# MCU.net
KiCad netlist of a schematic drawn in Altium Designer
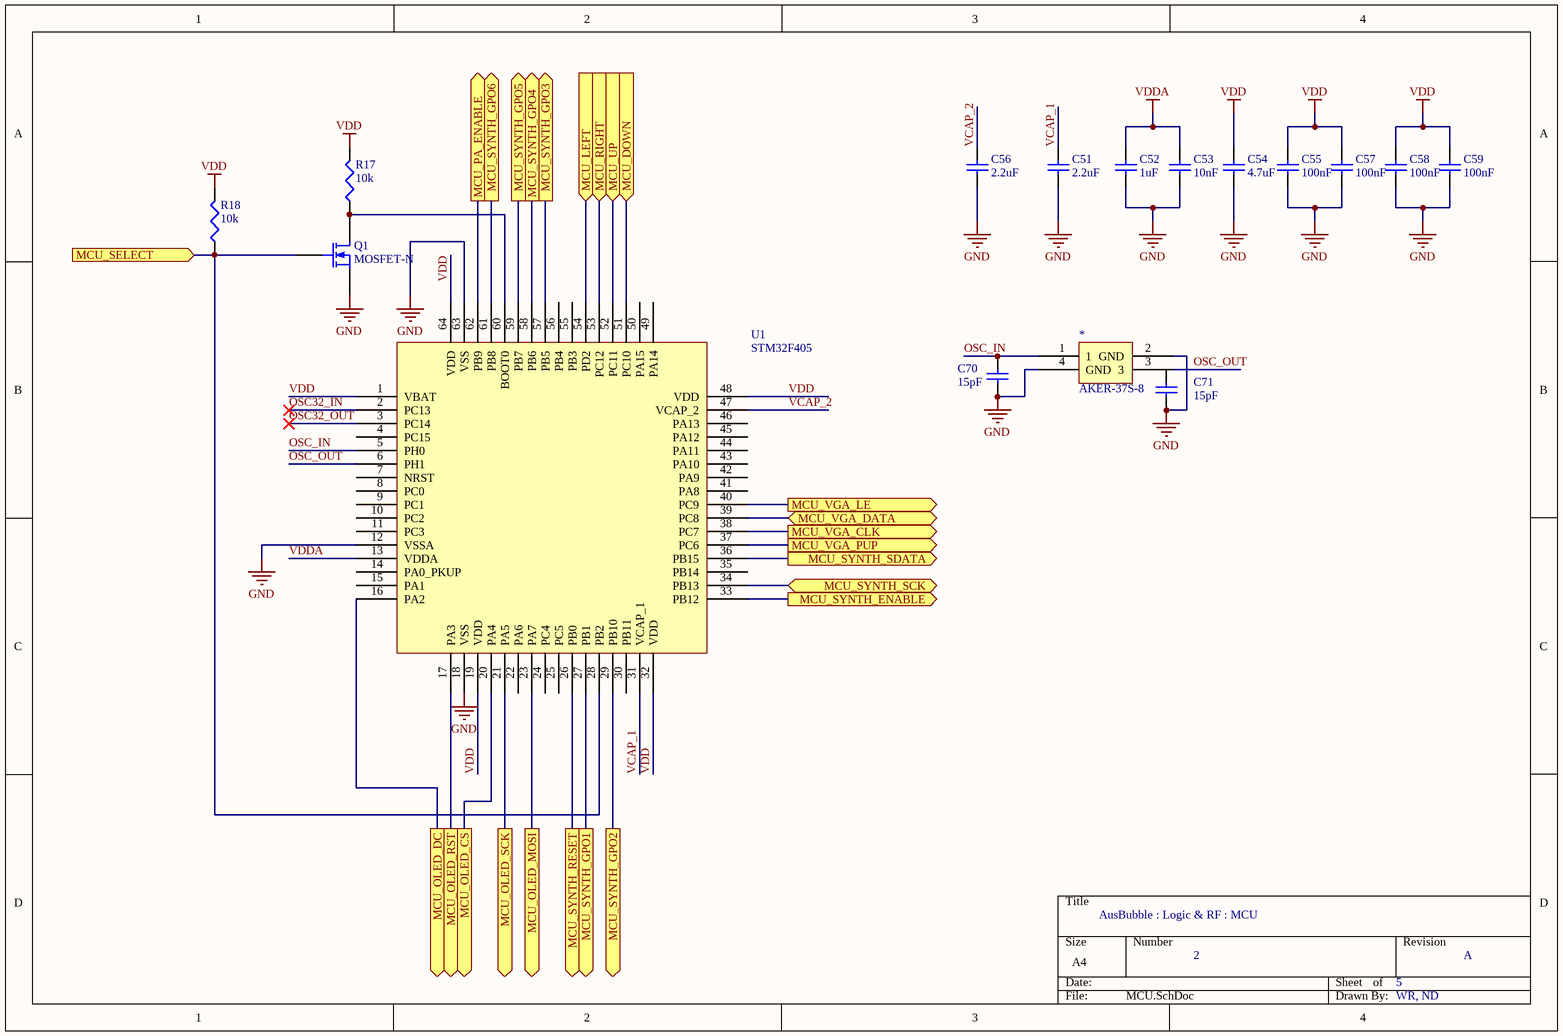
[diagram p0: MCU.SchDoc]

(export (version "E")
  (design (tool "Eeschema 10.0.6"))
  (components
    (comp (ref "*")
      (value "AKER-37S-8")
      (footprint "AKER-37S")
      (libsource (lib "Logic_RF_Component_Symbols") (part "AKER-37S-8"))
    )
    (comp (ref "C51")
      (value "2.2uF")
      (footprint "1608[0603]")
      (description "Capacitor (Semiconductor SIM Model)")
      (fields (field (name "Comment") "Cap Semi") (field (name "PUBLISHER") "Altium Limited"))
      (libsource (lib "Miscellaneous Devices") (part "Cap Semi"))
    )
    (comp (ref "C52")
      (value "1uF")
      (footprint "1608[0603]")
      (description "Capacitor (Semiconductor SIM Model)")
      (fields (field (name "Comment") "Cap Semi") (field (name "PUBLISHER") "Altium Limited"))
      (libsource (lib "Miscellaneous Devices") (part "Cap Semi"))
    )
    (comp (ref "C53")
      (value "10nF")
      (footprint "1608[0603]")
      (description "Capacitor (Semiconductor SIM Model)")
      (fields (field (name "Comment") "Cap Semi") (field (name "PUBLISHER") "Altium Limited"))
      (libsource (lib "Miscellaneous Devices") (part "Cap Semi"))
    )
    (comp (ref "C54")
      (value "4.7uF")
      (footprint "1608[0603]")
      (description "Capacitor (Semiconductor SIM Model)")
      (fields (field (name "Comment") "Cap Semi") (field (name "PUBLISHER") "Altium Limited"))
      (libsource (lib "Miscellaneous Devices") (part "Cap Semi"))
    )
    (comp (ref "C55")
      (value "100nF")
      (footprint "1608[0603]")
      (description "Capacitor (Semiconductor SIM Model)")
      (fields (field (name "Comment") "Cap Semi") (field (name "PUBLISHER") "Altium Limited"))
      (libsource (lib "Miscellaneous Devices") (part "Cap Semi"))
    )
    (comp (ref "C56")
      (value "2.2uF")
      (footprint "1608[0603]")
      (description "Capacitor (Semiconductor SIM Model)")
      (fields (field (name "Comment") "Cap Semi") (field (name "PUBLISHER") "Altium Limited"))
      (libsource (lib "Miscellaneous Devices") (part "Cap Semi"))
    )
    (comp (ref "C57")
      (value "100nF")
      (footprint "1608[0603]")
      (description "Capacitor (Semiconductor SIM Model)")
      (fields (field (name "Comment") "Cap Semi") (field (name "PUBLISHER") "Altium Limited"))
      (libsource (lib "Miscellaneous Devices") (part "Cap Semi"))
    )
    (comp (ref "C58")
      (value "100nF")
      (footprint "1608[0603]")
      (description "Capacitor (Semiconductor SIM Model)")
      (fields (field (name "Comment") "Cap Semi") (field (name "PUBLISHER") "Altium Limited"))
      (libsource (lib "Miscellaneous Devices") (part "Cap Semi"))
    )
    (comp (ref "C59")
      (value "100nF")
      (footprint "1608[0603]")
      (description "Capacitor (Semiconductor SIM Model)")
      (fields (field (name "Comment") "Cap Semi") (field (name "PUBLISHER") "Altium Limited"))
      (libsource (lib "Miscellaneous Devices") (part "Cap Semi"))
    )
    (comp (ref "C70")
      (value "15pF")
      (footprint "0402")
      (description "Capacitor (Semiconductor SIM Model)")
      (fields (field (name "Comment") "Cap Semi") (field (name "PUBLISHER") "Altium Limited"))
      (libsource (lib "Miscellaneous Devices") (part "Cap Semi"))
    )
    (comp (ref "C71")
      (value "15pF")
      (footprint "0402")
      (description "Capacitor (Semiconductor SIM Model)")
      (fields (field (name "Comment") "Cap Semi") (field (name "PUBLISHER") "Altium Limited"))
      (libsource (lib "Miscellaneous Devices") (part "Cap Semi"))
    )
    (comp (ref "Q1")
      (value "MOSFET-N")
      (footprint "SOT95P230-3M")
      (description "N-Channel MOSFET")
      (fields (field (name "PUBLISHER") "Altium Limited"))
      (libsource (lib "Miscellaneous Devices") (part "MOSFET-N"))
    )
    (comp (ref "R17")
      (value "10k")
      (footprint "J1-0603")
      (description "Resistor")
      (fields (field (name "Comment") "Res3") (field (name "PUBLISHER") "Altium Limited"))
      (libsource (lib "Miscellaneous Devices") (part "Res3"))
    )
    (comp (ref "R18")
      (value "10k")
      (footprint "J1-0603")
      (description "Resistor")
      (fields (field (name "Comment") "Res3") (field (name "PUBLISHER") "Altium Limited"))
      (libsource (lib "Miscellaneous Devices") (part "Res3"))
    )
    (comp (ref "U1")
      (value "STM32F405")
      (footprint "SQFP50P1200X1200-64L")
      (description "ARM Cortex-M4 32 bit Microprocessor")
      (libsource (lib "Logic_RF_Component_Symbols") (part "STM32F405RG"))
    )
  )
  (nets
    (net (code "1") (name "/MCU_DOWN") (class "Default")
      (node (ref "U1") (pin "51") (pinfunction "PC10_51") (pintype "passive"))
    )
    (net (code "2") (name "/MCU_LEFT") (class "Default")
      (node (ref "U1") (pin "54") (pinfunction "PD2_54") (pintype "passive"))
    )
    (net (code "3") (name "/MCU_OLED_CS") (class "Default")
      (node (ref "U1") (pin "20") (pinfunction "PA4_20") (pintype "passive"))
    )
    (net (code "4") (name "/MCU_OLED_DC") (class "Default")
      (node (ref "U1") (pin "16") (pinfunction "PA2_16") (pintype "passive"))
    )
    (net (code "5") (name "/MCU_OLED_MOSI") (class "Default")
      (node (ref "U1") (pin "23") (pinfunction "PA7_23") (pintype "passive"))
    )
    (net (code "6") (name "/MCU_OLED_RST") (class "Default")
      (node (ref "U1") (pin "17") (pinfunction "PA3_17") (pintype "passive"))
    )
    (net (code "7") (name "/MCU_OLED_SCK") (class "Default")
      (node (ref "U1") (pin "21") (pinfunction "PA5_21") (pintype "passive"))
    )
    (net (code "8") (name "/MCU_PA_ENABLE") (class "Default")
      (node (ref "U1") (pin "62") (pinfunction "PB9_62") (pintype "passive"))
    )
    (net (code "9") (name "/MCU_RIGHT") (class "Default")
      (node (ref "U1") (pin "53") (pinfunction "PC12_53") (pintype "passive"))
    )
    (net (code "10") (name "/MCU_SELECT") (class "Default")
      (node (ref "Q1") (pin "2") (pinfunction "G_2") (pintype "passive"))
      (node (ref "R18") (pin "1") (pinfunction "1_1") (pintype "passive"))
      (node (ref "U1") (pin "28") (pinfunction "PB2_28") (pintype "passive"))
    )
    (net (code "11") (name "/MCU_SYNTH_ENABLE") (class "Default")
      (node (ref "U1") (pin "33") (pinfunction "PB12_33") (pintype "passive"))
    )
    (net (code "12") (name "/MCU_SYNTH_GPO1") (class "Default")
      (node (ref "U1") (pin "27") (pinfunction "PB1_27") (pintype "passive"))
    )
    (net (code "13") (name "/MCU_SYNTH_GPO2") (class "Default")
      (node (ref "U1") (pin "29") (pinfunction "PB10_29") (pintype "passive"))
    )
    (net (code "14") (name "/MCU_SYNTH_GPO3") (class "Default")
      (node (ref "U1") (pin "57") (pinfunction "PB5_57") (pintype "passive"))
    )
    (net (code "15") (name "/MCU_SYNTH_GPO4") (class "Default")
      (node (ref "U1") (pin "58") (pinfunction "PB6_58") (pintype "passive"))
    )
    (net (code "16") (name "/MCU_SYNTH_GPO5") (class "Default")
      (node (ref "U1") (pin "59") (pinfunction "PB7_59") (pintype "passive"))
    )
    (net (code "17") (name "/MCU_SYNTH_GPO6") (class "Default")
      (node (ref "U1") (pin "61") (pinfunction "PB8_61") (pintype "passive"))
    )
    (net (code "18") (name "/MCU_SYNTH_RESET") (class "Default")
      (node (ref "U1") (pin "26") (pinfunction "PB0_26") (pintype "passive"))
    )
    (net (code "19") (name "/MCU_SYNTH_SCK") (class "Default")
      (node (ref "U1") (pin "34") (pinfunction "PB13_34") (pintype "passive"))
    )
    (net (code "20") (name "/MCU_SYNTH_SDATA") (class "Default")
      (node (ref "U1") (pin "36") (pinfunction "PB15_36") (pintype "passive"))
    )
    (net (code "21") (name "/MCU_UP") (class "Default")
      (node (ref "U1") (pin "52") (pinfunction "PC11_52") (pintype "passive"))
    )
    (net (code "22") (name "/MCU_VGA_CLK") (class "Default")
      (node (ref "U1") (pin "38") (pinfunction "PC7_38") (pintype "passive"))
    )
    (net (code "23") (name "/MCU_VGA_DATA") (class "Default")
      (node (ref "U1") (pin "39") (pinfunction "PC8_39") (pintype "passive"))
    )
    (net (code "24") (name "/MCU_VGA_LE") (class "Default")
      (node (ref "U1") (pin "40") (pinfunction "PC9_40") (pintype "passive"))
    )
    (net (code "25") (name "/MCU_VGA_PUP") (class "Default")
      (node (ref "U1") (pin "37") (pinfunction "PC6_37") (pintype "passive"))
    )
    (net (code "26") (name "/OSC32_IN") (class "Default")
      (node (ref "U1") (pin "2") (pinfunction "PC13_2") (pintype "passive+no_connect"))
    )
    (net (code "27") (name "/OSC32_OUT") (class "Default")
      (node (ref "U1") (pin "3") (pinfunction "PC14_3") (pintype "passive+no_connect"))
    )
    (net (code "28") (name "/OSC_IN") (class "Default")
      (node (ref "*") (pin "1") (pinfunction "1_1") (pintype "passive"))
      (node (ref "C70") (pin "2") (pinfunction "2_2") (pintype "passive"))
      (node (ref "U1") (pin "5") (pinfunction "PH0_5") (pintype "passive"))
    )
    (net (code "29") (name "/OSC_OUT") (class "Default")
      (node (ref "*") (pin "3") (pinfunction "3_3") (pintype "passive"))
      (node (ref "U1") (pin "6") (pinfunction "PH1_6") (pintype "passive"))
    )
    (net (code "30") (name "/VCAP_1") (class "Default")
      (node (ref "C51") (pin "2") (pinfunction "2_2") (pintype "passive"))
      (node (ref "U1") (pin "31") (pinfunction "VCAP_1_31") (pintype "passive"))
    )
    (net (code "31") (name "/VCAP_2") (class "Default")
      (node (ref "C56") (pin "2") (pinfunction "2_2") (pintype "passive"))
      (node (ref "U1") (pin "47") (pinfunction "VCAP_2_47") (pintype "passive"))
    )
    (net (code "32") (name "GND") (class "Default")
      (node (ref "*") (pin "2") (pinfunction "GND_2") (pintype "passive"))
      (node (ref "*") (pin "4") (pinfunction "GND_4") (pintype "passive"))
      (node (ref "C51") (pin "1") (pinfunction "1_1") (pintype "passive"))
      (node (ref "C52") (pin "1") (pinfunction "1_1") (pintype "passive"))
      (node (ref "C53") (pin "1") (pinfunction "1_1") (pintype "passive"))
      (node (ref "C54") (pin "1") (pinfunction "1_1") (pintype "passive"))
      (node (ref "C55") (pin "1") (pinfunction "1_1") (pintype "passive"))
      (node (ref "C56") (pin "1") (pinfunction "1_1") (pintype "passive"))
      (node (ref "C57") (pin "1") (pinfunction "1_1") (pintype "passive"))
      (node (ref "C58") (pin "1") (pinfunction "1_1") (pintype "passive"))
      (node (ref "C59") (pin "1") (pinfunction "1_1") (pintype "passive"))
      (node (ref "C70") (pin "1") (pinfunction "1_1") (pintype "passive"))
      (node (ref "C71") (pin "1") (pinfunction "1_1") (pintype "passive"))
      (node (ref "Q1") (pin "3") (pinfunction "S_3") (pintype "passive"))
      (node (ref "U1") (pin "12") (pinfunction "VSSA_12") (pintype "passive"))
      (node (ref "U1") (pin "18") (pinfunction "VSS_18") (pintype "passive"))
      (node (ref "U1") (pin "63") (pinfunction "VSS_63") (pintype "passive"))
    )
    (net (code "33") (name "Net-(Q1-D)") (class "Default")
      (node (ref "Q1") (pin "1") (pinfunction "D_1") (pintype "passive"))
      (node (ref "R17") (pin "1") (pinfunction "1_1") (pintype "passive"))
      (node (ref "U1") (pin "60") (pinfunction "BOOT0_60") (pintype "passive"))
    )
    (net (code "34") (name "VDD") (class "Default")
      (node (ref "C54") (pin "2") (pinfunction "2_2") (pintype "passive"))
      (node (ref "C55") (pin "2") (pinfunction "2_2") (pintype "passive"))
      (node (ref "C57") (pin "2") (pinfunction "2_2") (pintype "passive"))
      (node (ref "C58") (pin "2") (pinfunction "2_2") (pintype "passive"))
      (node (ref "C59") (pin "2") (pinfunction "2_2") (pintype "passive"))
      (node (ref "R17") (pin "2") (pinfunction "2_2") (pintype "passive"))
      (node (ref "R18") (pin "2") (pinfunction "2_2") (pintype "passive"))
      (node (ref "U1") (pin "1") (pinfunction "VBAT_1") (pintype "passive"))
      (node (ref "U1") (pin "19") (pinfunction "VDD_19") (pintype "passive"))
      (node (ref "U1") (pin "32") (pinfunction "VDD_32") (pintype "passive"))
      (node (ref "U1") (pin "48") (pinfunction "VDD_48") (pintype "passive"))
      (node (ref "U1") (pin "64") (pinfunction "VDD_64") (pintype "passive"))
    )
    (net (code "35") (name "VDDA") (class "Default")
      (node (ref "C52") (pin "2") (pinfunction "2_2") (pintype "passive"))
      (node (ref "C53") (pin "2") (pinfunction "2_2") (pintype "passive"))
      (node (ref "U1") (pin "13") (pinfunction "VDDA_13") (pintype "passive"))
    )
    (net (code "36") (name "unconnected-(C71-Pad2)") (class "Default")
      (node (ref "C71") (pin "2") (pinfunction "2_2") (pintype "passive"))
    )
    (net (code "37") (name "unconnected-(U1-NRST-Pad7)") (class "Default")
      (node (ref "U1") (pin "7") (pinfunction "NRST_7") (pintype "passive"))
    )
    (net (code "38") (name "unconnected-(U1-PA0_PKUP-Pad14)") (class "Default")
      (node (ref "U1") (pin "14") (pinfunction "PA0_PKUP_14") (pintype "passive"))
    )
    (net (code "39") (name "unconnected-(U1-PA1-Pad15)") (class "Default")
      (node (ref "U1") (pin "15") (pinfunction "PA1_15") (pintype "passive"))
    )
    (net (code "40") (name "unconnected-(U1-PA6-Pad22)") (class "Default")
      (node (ref "U1") (pin "22") (pinfunction "PA6_22") (pintype "passive"))
    )
    (net (code "41") (name "unconnected-(U1-PA8-Pad41)") (class "Default")
      (node (ref "U1") (pin "41") (pinfunction "PA8_41") (pintype "passive"))
    )
    (net (code "42") (name "unconnected-(U1-PA9-Pad42)") (class "Default")
      (node (ref "U1") (pin "42") (pinfunction "PA9_42") (pintype "passive"))
    )
    (net (code "43") (name "unconnected-(U1-PA10-Pad43)") (class "Default")
      (node (ref "U1") (pin "43") (pinfunction "PA10_43") (pintype "passive"))
    )
    (net (code "44") (name "unconnected-(U1-PA11-Pad44)") (class "Default")
      (node (ref "U1") (pin "44") (pinfunction "PA11_44") (pintype "passive"))
    )
    (net (code "45") (name "unconnected-(U1-PA12-Pad45)") (class "Default")
      (node (ref "U1") (pin "45") (pinfunction "PA12_45") (pintype "passive"))
    )
    (net (code "46") (name "unconnected-(U1-PA13-Pad46)") (class "Default")
      (node (ref "U1") (pin "46") (pinfunction "PA13_46") (pintype "passive"))
    )
    (net (code "47") (name "unconnected-(U1-PA14-Pad49)") (class "Default")
      (node (ref "U1") (pin "49") (pinfunction "PA14_49") (pintype "passive"))
    )
    (net (code "48") (name "unconnected-(U1-PA15-Pad50)") (class "Default")
      (node (ref "U1") (pin "50") (pinfunction "PA15_50") (pintype "passive"))
    )
    (net (code "49") (name "unconnected-(U1-PB3-Pad55)") (class "Default")
      (node (ref "U1") (pin "55") (pinfunction "PB3_55") (pintype "passive"))
    )
    (net (code "50") (name "unconnected-(U1-PB4-Pad56)") (class "Default")
      (node (ref "U1") (pin "56") (pinfunction "PB4_56") (pintype "passive"))
    )
    (net (code "51") (name "unconnected-(U1-PB11-Pad30)") (class "Default")
      (node (ref "U1") (pin "30") (pinfunction "PB11_30") (pintype "passive"))
    )
    (net (code "52") (name "unconnected-(U1-PB14-Pad35)") (class "Default")
      (node (ref "U1") (pin "35") (pinfunction "PB14_35") (pintype "passive"))
    )
    (net (code "53") (name "unconnected-(U1-PC0-Pad8)") (class "Default")
      (node (ref "U1") (pin "8") (pinfunction "PC0_8") (pintype "passive"))
    )
    (net (code "54") (name "unconnected-(U1-PC1-Pad9)") (class "Default")
      (node (ref "U1") (pin "9") (pinfunction "PC1_9") (pintype "passive"))
    )
    (net (code "55") (name "unconnected-(U1-PC2-Pad10)") (class "Default")
      (node (ref "U1") (pin "10") (pinfunction "PC2_10") (pintype "passive"))
    )
    (net (code "56") (name "unconnected-(U1-PC3-Pad11)") (class "Default")
      (node (ref "U1") (pin "11") (pinfunction "PC3_11") (pintype "passive"))
    )
    (net (code "57") (name "unconnected-(U1-PC4-Pad24)") (class "Default")
      (node (ref "U1") (pin "24") (pinfunction "PC4_24") (pintype "passive"))
    )
    (net (code "58") (name "unconnected-(U1-PC5-Pad25)") (class "Default")
      (node (ref "U1") (pin "25") (pinfunction "PC5_25") (pintype "passive"))
    )
    (net (code "59") (name "unconnected-(U1-PC15-Pad4)") (class "Default")
      (node (ref "U1") (pin "4") (pinfunction "PC15_4") (pintype "passive"))
    )
  )
)
